# sampahSIM.net
KiCad netlist of a schematic drawn in EAGLE
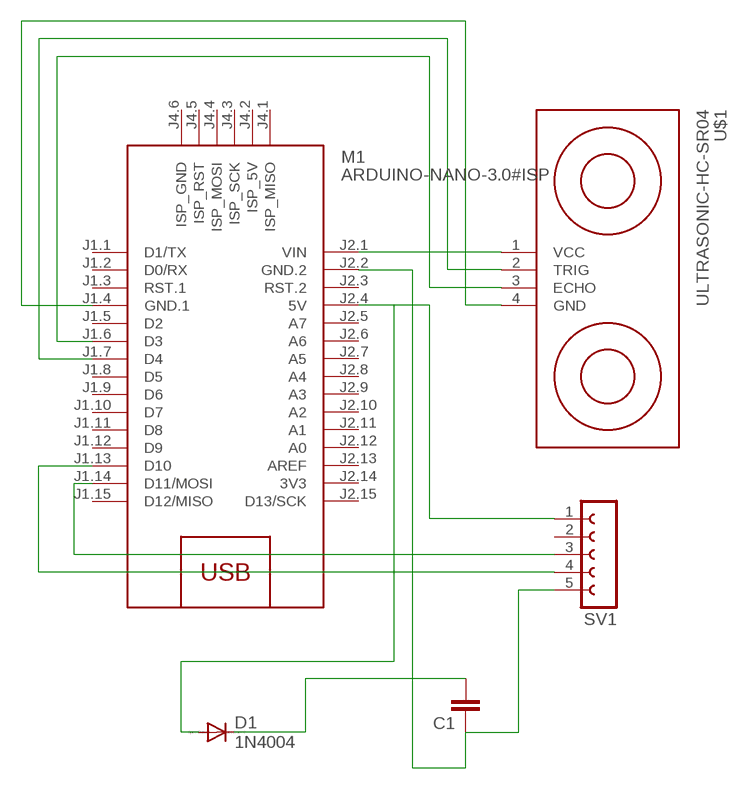
[diagram p0: schematic, sheet 1]

(export (version "E")
  (design (tool "Eeschema 10.0.6"))
  (components
    (comp (ref "C1")
      (value "C2,5-3")
      (footprint "eagle-import:C2.5-3")
      (libsource (lib "eagle-import") (part "C2,5-3"))
    )
    (comp (ref "D1")
      (value "1N4004")
      (footprint "eagle-import:DO41-10")
      (libsource (lib "eagle-import") (part "1N4004"))
    )
    (comp (ref "M1")
      (value "ARDUINO-NANO-3.0#ISP")
      (footprint "eagle-import:ARDUINO-NANO-3.0#ISP")
      (libsource (lib "eagle-import") (part "ARDUINO-NANO-3.0#ISP"))
    )
    (comp (ref "SV1")
      (value "FE05-1")
      (footprint "eagle-import:FE05-1")
      (libsource (lib "eagle-import") (part "FE05-1"))
    )
    (comp (ref "U$1")
      (value "ULTRASONIC-HC-SR04")
      (footprint "eagle-import:ULTRASONIC-HC-SR04")
      (libsource (lib "eagle-import") (part "ULTRASONIC-HC-SR04"))
    )
  )
  (nets
    (net (code "1") (name "/3V3") (class "Default")
      (node (ref "M1") (pin "J2.14") (pinfunction "3V3_J2.14") (pintype "power_in"))
    )
    (net (code "2") (name "Net-(C1-Pad2)") (class "Default")
      (node (ref "C1") (pin "2") (pinfunction "2_2") (pintype "passive"))
      (node (ref "D1") (pin "C") (pinfunction "C_C") (pintype "passive"))
    )
    (net (code "3") (name "Net-(M1-5V)") (class "Default")
      (node (ref "D1") (pin "A") (pinfunction "A_A") (pintype "passive"))
      (node (ref "M1") (pin "J2.4") (pinfunction "5V_J2.4") (pintype "power_in"))
      (node (ref "SV1") (pin "1") (pinfunction "1_1") (pintype "passive"))
    )
    (net (code "4") (name "Net-(M1-D3)") (class "Default")
      (node (ref "M1") (pin "J1.6") (pinfunction "D3_J1.6") (pintype "bidirectional"))
      (node (ref "U$1") (pin "3") (pinfunction "ECHO_3") (pintype "output"))
    )
    (net (code "5") (name "Net-(M1-D4)") (class "Default")
      (node (ref "M1") (pin "J1.7") (pinfunction "D4_J1.7") (pintype "bidirectional"))
      (node (ref "U$1") (pin "2") (pinfunction "TRIG_2") (pintype "input"))
    )
    (net (code "6") (name "Net-(M1-D10)") (class "Default")
      (node (ref "M1") (pin "J1.13") (pinfunction "D10_J1.13") (pintype "bidirectional"))
      (node (ref "SV1") (pin "4") (pinfunction "4_4") (pintype "passive"))
    )
    (net (code "7") (name "Net-(M1-D11{slash}MOSI)") (class "Default")
      (node (ref "M1") (pin "J1.14") (pinfunction "D11/MOSI_J1.14") (pintype "bidirectional"))
      (node (ref "SV1") (pin "3") (pinfunction "3_3") (pintype "passive"))
    )
    (net (code "8") (name "Net-(M1-GND.1)") (class "Default")
      (node (ref "M1") (pin "J1.4") (pinfunction "GND.1_J1.4") (pintype "power_in"))
      (node (ref "U$1") (pin "4") (pinfunction "GND_4") (pintype "power_in"))
    )
    (net (code "9") (name "Net-(M1-GND.2)") (class "Default")
      (node (ref "C1") (pin "1") (pinfunction "1_1") (pintype "passive"))
      (node (ref "M1") (pin "J2.2") (pinfunction "GND.2_J2.2") (pintype "power_in"))
      (node (ref "SV1") (pin "5") (pinfunction "5_5") (pintype "passive"))
    )
    (net (code "10") (name "Net-(M1-VIN)") (class "Default")
      (node (ref "M1") (pin "J2.1") (pinfunction "VIN_J2.1") (pintype "power_in"))
      (node (ref "U$1") (pin "1") (pinfunction "VCC_1") (pintype "power_in"))
    )
    (net (code "11") (name "unconnected-(M1-A0-PadJ2.12)") (class "Default")
      (node (ref "M1") (pin "J2.12") (pinfunction "A0_J2.12") (pintype "bidirectional"))
    )
    (net (code "12") (name "unconnected-(M1-A1-PadJ2.11)") (class "Default")
      (node (ref "M1") (pin "J2.11") (pinfunction "A1_J2.11") (pintype "bidirectional"))
    )
    (net (code "13") (name "unconnected-(M1-A2-PadJ2.10)") (class "Default")
      (node (ref "M1") (pin "J2.10") (pinfunction "A2_J2.10") (pintype "bidirectional"))
    )
    (net (code "14") (name "unconnected-(M1-A3-PadJ2.9)") (class "Default")
      (node (ref "M1") (pin "J2.9") (pinfunction "A3_J2.9") (pintype "bidirectional"))
    )
    (net (code "15") (name "unconnected-(M1-A4-PadJ2.8)") (class "Default")
      (node (ref "M1") (pin "J2.8") (pinfunction "A4_J2.8") (pintype "bidirectional"))
    )
    (net (code "16") (name "unconnected-(M1-A5-PadJ2.7)") (class "Default")
      (node (ref "M1") (pin "J2.7") (pinfunction "A5_J2.7") (pintype "bidirectional"))
    )
    (net (code "17") (name "unconnected-(M1-A6-PadJ2.6)") (class "Default")
      (node (ref "M1") (pin "J2.6") (pinfunction "A6_J2.6") (pintype "bidirectional"))
    )
    (net (code "18") (name "unconnected-(M1-A7-PadJ2.5)") (class "Default")
      (node (ref "M1") (pin "J2.5") (pinfunction "A7_J2.5") (pintype "bidirectional"))
    )
    (net (code "19") (name "unconnected-(M1-AREF-PadJ2.13)") (class "Default")
      (node (ref "M1") (pin "J2.13") (pinfunction "AREF_J2.13") (pintype "bidirectional"))
    )
    (net (code "20") (name "unconnected-(M1-D0{slash}RX-PadJ1.2)") (class "Default")
      (node (ref "M1") (pin "J1.2") (pinfunction "D0/RX_J1.2") (pintype "bidirectional"))
    )
    (net (code "21") (name "unconnected-(M1-D1{slash}TX-PadJ1.1)") (class "Default")
      (node (ref "M1") (pin "J1.1") (pinfunction "D1/TX_J1.1") (pintype "bidirectional"))
    )
    (net (code "22") (name "unconnected-(M1-D2-PadJ1.5)") (class "Default")
      (node (ref "M1") (pin "J1.5") (pinfunction "D2_J1.5") (pintype "bidirectional"))
    )
    (net (code "23") (name "unconnected-(M1-D5-PadJ1.8)") (class "Default")
      (node (ref "M1") (pin "J1.8") (pinfunction "D5_J1.8") (pintype "bidirectional"))
    )
    (net (code "24") (name "unconnected-(M1-D6-PadJ1.9)") (class "Default")
      (node (ref "M1") (pin "J1.9") (pinfunction "D6_J1.9") (pintype "bidirectional"))
    )
    (net (code "25") (name "unconnected-(M1-D7-PadJ1.10)") (class "Default")
      (node (ref "M1") (pin "J1.10") (pinfunction "D7_J1.10") (pintype "bidirectional"))
    )
    (net (code "26") (name "unconnected-(M1-D8-PadJ1.11)") (class "Default")
      (node (ref "M1") (pin "J1.11") (pinfunction "D8_J1.11") (pintype "bidirectional"))
    )
    (net (code "27") (name "unconnected-(M1-D9-PadJ1.12)") (class "Default")
      (node (ref "M1") (pin "J1.12") (pinfunction "D9_J1.12") (pintype "bidirectional"))
    )
    (net (code "28") (name "unconnected-(M1-D12{slash}MISO-PadJ1.15)") (class "Default")
      (node (ref "M1") (pin "J1.15") (pinfunction "D12/MISO_J1.15") (pintype "bidirectional"))
    )
    (net (code "29") (name "unconnected-(M1-D13{slash}SCK-PadJ2.15)") (class "Default")
      (node (ref "M1") (pin "J2.15") (pinfunction "D13/SCK_J2.15") (pintype "bidirectional"))
    )
    (net (code "30") (name "unconnected-(M1-ISP_5V-PadJ4.2)") (class "Default")
      (node (ref "M1") (pin "J4.2") (pinfunction "ISP_5V_J4.2") (pintype "bidirectional"))
    )
    (net (code "31") (name "unconnected-(M1-ISP_GND-PadJ4.6)") (class "Default")
      (node (ref "M1") (pin "J4.6") (pinfunction "ISP_GND_J4.6") (pintype "bidirectional"))
    )
    (net (code "32") (name "unconnected-(M1-ISP_MISO-PadJ4.1)") (class "Default")
      (node (ref "M1") (pin "J4.1") (pinfunction "ISP_MISO_J4.1") (pintype "bidirectional"))
    )
    (net (code "33") (name "unconnected-(M1-ISP_MOSI-PadJ4.4)") (class "Default")
      (node (ref "M1") (pin "J4.4") (pinfunction "ISP_MOSI_J4.4") (pintype "bidirectional"))
    )
    (net (code "34") (name "unconnected-(M1-ISP_RST-PadJ4.5)") (class "Default")
      (node (ref "M1") (pin "J4.5") (pinfunction "ISP_RST_J4.5") (pintype "bidirectional"))
    )
    (net (code "35") (name "unconnected-(M1-ISP_SCK-PadJ4.3)") (class "Default")
      (node (ref "M1") (pin "J4.3") (pinfunction "ISP_SCK_J4.3") (pintype "bidirectional"))
    )
    (net (code "36") (name "unconnected-(M1-RST.1-PadJ1.3)") (class "Default")
      (node (ref "M1") (pin "J1.3") (pinfunction "RST.1_J1.3") (pintype "bidirectional"))
    )
    (net (code "37") (name "unconnected-(M1-RST.2-PadJ2.3)") (class "Default")
      (node (ref "M1") (pin "J2.3") (pinfunction "RST.2_J2.3") (pintype "bidirectional"))
    )
    (net (code "38") (name "unconnected-(SV1-Pad2)") (class "Default")
      (node (ref "SV1") (pin "2") (pinfunction "2_2") (pintype "passive"))
    )
  )
)
